# Prototipo_3X.net
KiCad netlist of a schematic drawn in EAGLE
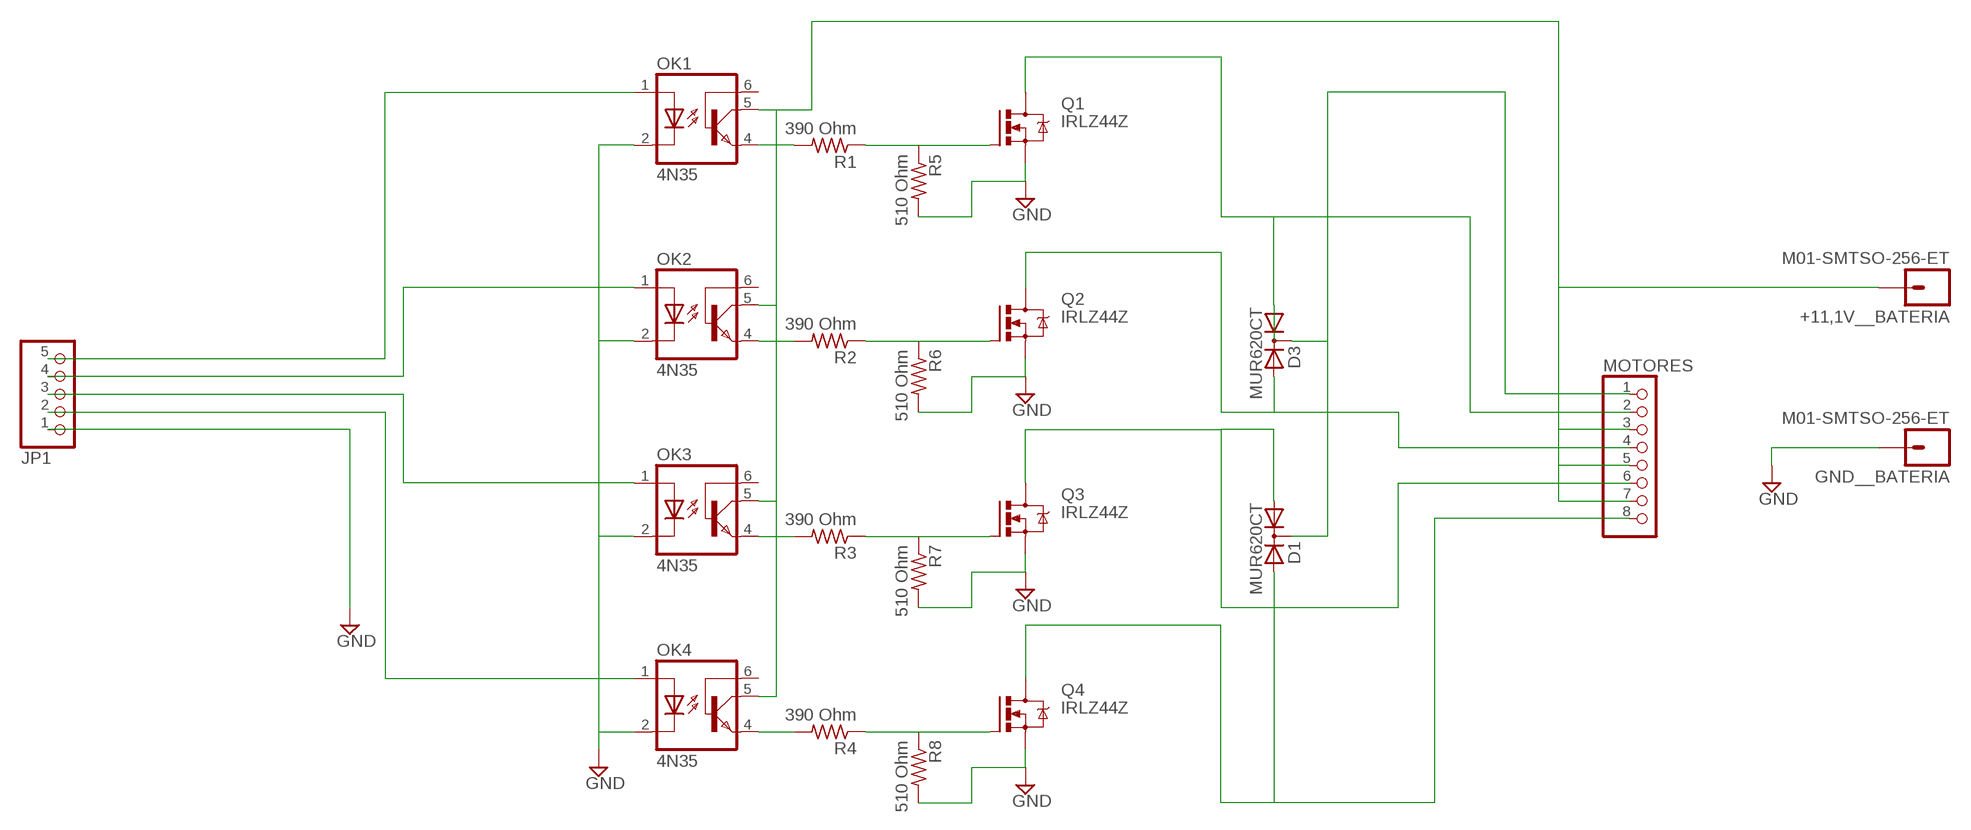
[diagram p0: schematic, sheet 1]

(export (version "E")
  (design (tool "Eeschema 10.0.6"))
  (components
    (comp (ref "+11,1V__BATERIA")
      (value "M01-SMTSO-256-ET")
      (footprint "eagle-import:SMTSO-256-ET")
      (libsource (lib "eagle-import") (part "M01-SMTSO-256-ET"))
    )
    (comp (ref "D1")
      (value "MUR620CT")
      (footprint "eagle-import:TO220AB")
      (libsource (lib "eagle-import") (part "MUR620CT"))
    )
    (comp (ref "D3")
      (value "MUR620CT")
      (footprint "eagle-import:TO220AB")
      (libsource (lib "eagle-import") (part "MUR620CT"))
    )
    (comp (ref "GND__BATERIA")
      (value "M01-SMTSO-256-ET")
      (footprint "eagle-import:SMTSO-256-ET")
      (libsource (lib "eagle-import") (part "M01-SMTSO-256-ET"))
    )
    (comp (ref "JP1")
      (value "PINHD-1X5/90")
      (footprint "eagle-import:1X05_90")
      (libsource (lib "eagle-import") (part "PINHD-1X5/90"))
    )
    (comp (ref "MOTORES")
      (value "PINHD-1X8/90")
      (footprint "eagle-import:1X08_90")
      (libsource (lib "eagle-import") (part "PINHD-1X8/90"))
    )
    (comp (ref "OK1")
      (value "4N35")
      (footprint "eagle-import:DIL06")
      (fields (field (name "MF") "FAIRCHILD SEMICONDUCTOR"))
      (libsource (lib "eagle-import") (part "4N35"))
    )
    (comp (ref "OK2")
      (value "4N35")
      (footprint "eagle-import:DIL06")
      (fields (field (name "MF") "FAIRCHILD SEMICONDUCTOR"))
      (libsource (lib "eagle-import") (part "4N35"))
    )
    (comp (ref "OK3")
      (value "4N35")
      (footprint "eagle-import:DIL06")
      (fields (field (name "MF") "FAIRCHILD SEMICONDUCTOR"))
      (libsource (lib "eagle-import") (part "4N35"))
    )
    (comp (ref "OK4")
      (value "4N35")
      (footprint "eagle-import:DIL06")
      (fields (field (name "MF") "FAIRCHILD SEMICONDUCTOR"))
      (libsource (lib "eagle-import") (part "4N35"))
    )
    (comp (ref "Q1")
      (value "IRLZ44Z")
      (footprint "eagle-import:TO220BH")
      (libsource (lib "eagle-import") (part "IRLZ44Z"))
    )
    (comp (ref "Q2")
      (value "IRLZ44Z")
      (footprint "eagle-import:TO220BH")
      (libsource (lib "eagle-import") (part "IRLZ44Z"))
    )
    (comp (ref "Q3")
      (value "IRLZ44Z")
      (footprint "eagle-import:TO220BH")
      (libsource (lib "eagle-import") (part "IRLZ44Z"))
    )
    (comp (ref "Q4")
      (value "IRLZ44Z")
      (footprint "eagle-import:TO220BH")
      (libsource (lib "eagle-import") (part "IRLZ44Z"))
    )
    (comp (ref "R1")
      (value "390 Ohm")
      (footprint "eagle-import:0207_7")
      (libsource (lib "eagle-import") (part "R-US_0207/7"))
    )
    (comp (ref "R2")
      (value "390 Ohm")
      (footprint "eagle-import:0207_7")
      (libsource (lib "eagle-import") (part "R-US_0207/7"))
    )
    (comp (ref "R3")
      (value "390 Ohm")
      (footprint "eagle-import:0207_7")
      (libsource (lib "eagle-import") (part "R-US_0207/7"))
    )
    (comp (ref "R4")
      (value "390 Ohm")
      (footprint "eagle-import:0207_7")
      (libsource (lib "eagle-import") (part "R-US_0207/7"))
    )
    (comp (ref "R5")
      (value "510 Ohm")
      (footprint "eagle-import:0207_7")
      (libsource (lib "eagle-import") (part "R-US_0207/7"))
    )
    (comp (ref "R6")
      (value "510 Ohm")
      (footprint "eagle-import:0207_7")
      (libsource (lib "eagle-import") (part "R-US_0207/7"))
    )
    (comp (ref "R7")
      (value "510 Ohm")
      (footprint "eagle-import:0207_7")
      (libsource (lib "eagle-import") (part "R-US_0207/7"))
    )
    (comp (ref "R8")
      (value "510 Ohm")
      (footprint "eagle-import:0207_7")
      (libsource (lib "eagle-import") (part "R-US_0207/7"))
    )
  )
  (nets
    (net (code "1") (name "GND") (class "Default")
      (node (ref "GND__BATERIA") (pin "P$1") (pinfunction "1_P$1") (pintype "passive"))
      (node (ref "JP1") (pin "1") (pinfunction "1_1") (pintype "passive"))
      (node (ref "OK1") (pin "2") (pinfunction "C_2") (pintype "passive"))
      (node (ref "OK2") (pin "2") (pinfunction "C_2") (pintype "passive"))
      (node (ref "OK3") (pin "2") (pinfunction "C_2") (pintype "passive"))
      (node (ref "OK4") (pin "2") (pinfunction "C_2") (pintype "passive"))
      (node (ref "Q1") (pin "S") (pinfunction "S_S") (pintype "passive"))
      (node (ref "Q2") (pin "S") (pinfunction "S_S") (pintype "passive"))
      (node (ref "Q3") (pin "S") (pinfunction "S_S") (pintype "passive"))
      (node (ref "Q4") (pin "S") (pinfunction "S_S") (pintype "passive"))
      (node (ref "R5") (pin "2") (pinfunction "2_2") (pintype "passive"))
      (node (ref "R6") (pin "2") (pinfunction "2_2") (pintype "passive"))
      (node (ref "R7") (pin "2") (pinfunction "2_2") (pintype "passive"))
      (node (ref "R8") (pin "2") (pinfunction "2_2") (pintype "passive"))
    )
    (net (code "2") (name "Net-(+11,1V__BATERIA-1)") (class "Default")
      (node (ref "+11,1V__BATERIA") (pin "P$1") (pinfunction "1_P$1") (pintype "passive"))
      (node (ref "D1") (pin "C") (pinfunction "C_C") (pintype "passive"))
      (node (ref "D3") (pin "C") (pinfunction "C_C") (pintype "passive"))
      (node (ref "MOTORES") (pin "1") (pinfunction "1_1") (pintype "passive"))
      (node (ref "MOTORES") (pin "3") (pinfunction "3_3") (pintype "passive"))
      (node (ref "MOTORES") (pin "5") (pinfunction "5_5") (pintype "passive"))
      (node (ref "MOTORES") (pin "7") (pinfunction "7_7") (pintype "passive"))
      (node (ref "OK1") (pin "5") (pinfunction "COL_5") (pintype "passive"))
      (node (ref "OK2") (pin "5") (pinfunction "COL_5") (pintype "passive"))
      (node (ref "OK3") (pin "5") (pinfunction "COL_5") (pintype "passive"))
      (node (ref "OK4") (pin "5") (pinfunction "COL_5") (pintype "passive"))
    )
    (net (code "3") (name "Net-(D1-PadA1)") (class "Default")
      (node (ref "D1") (pin "A1") (pinfunction "A1_A1") (pintype "passive"))
      (node (ref "MOTORES") (pin "6") (pinfunction "6_6") (pintype "passive"))
      (node (ref "Q3") (pin "D") (pinfunction "D_D") (pintype "passive"))
    )
    (net (code "4") (name "Net-(D1-PadA2)") (class "Default")
      (node (ref "D1") (pin "A2") (pinfunction "A2_A2") (pintype "passive"))
      (node (ref "MOTORES") (pin "8") (pinfunction "8_8") (pintype "passive"))
      (node (ref "Q4") (pin "D") (pinfunction "D_D") (pintype "passive"))
    )
    (net (code "5") (name "Net-(D3-PadA1)") (class "Default")
      (node (ref "D3") (pin "A1") (pinfunction "A1_A1") (pintype "passive"))
      (node (ref "MOTORES") (pin "2") (pinfunction "2_2") (pintype "passive"))
      (node (ref "Q1") (pin "D") (pinfunction "D_D") (pintype "passive"))
    )
    (net (code "6") (name "Net-(D3-PadA2)") (class "Default")
      (node (ref "D3") (pin "A2") (pinfunction "A2_A2") (pintype "passive"))
      (node (ref "MOTORES") (pin "4") (pinfunction "4_4") (pintype "passive"))
      (node (ref "Q2") (pin "D") (pinfunction "D_D") (pintype "passive"))
    )
    (net (code "7") (name "Net-(OK1-A)") (class "Default")
      (node (ref "JP1") (pin "5") (pinfunction "5_5") (pintype "passive"))
      (node (ref "OK1") (pin "1") (pinfunction "A_1") (pintype "passive"))
    )
    (net (code "8") (name "Net-(OK1-EMI)") (class "Default")
      (node (ref "OK1") (pin "4") (pinfunction "EMI_4") (pintype "passive"))
      (node (ref "R1") (pin "2") (pinfunction "2_2") (pintype "passive"))
    )
    (net (code "9") (name "Net-(OK2-A)") (class "Default")
      (node (ref "JP1") (pin "4") (pinfunction "4_4") (pintype "passive"))
      (node (ref "OK2") (pin "1") (pinfunction "A_1") (pintype "passive"))
    )
    (net (code "10") (name "Net-(OK2-EMI)") (class "Default")
      (node (ref "OK2") (pin "4") (pinfunction "EMI_4") (pintype "passive"))
      (node (ref "R2") (pin "2") (pinfunction "2_2") (pintype "passive"))
    )
    (net (code "11") (name "Net-(OK3-A)") (class "Default")
      (node (ref "JP1") (pin "3") (pinfunction "3_3") (pintype "passive"))
      (node (ref "OK3") (pin "1") (pinfunction "A_1") (pintype "passive"))
    )
    (net (code "12") (name "Net-(OK3-EMI)") (class "Default")
      (node (ref "OK3") (pin "4") (pinfunction "EMI_4") (pintype "passive"))
      (node (ref "R3") (pin "2") (pinfunction "2_2") (pintype "passive"))
    )
    (net (code "13") (name "Net-(OK4-A)") (class "Default")
      (node (ref "JP1") (pin "2") (pinfunction "2_2") (pintype "passive"))
      (node (ref "OK4") (pin "1") (pinfunction "A_1") (pintype "passive"))
    )
    (net (code "14") (name "Net-(OK4-EMI)") (class "Default")
      (node (ref "OK4") (pin "4") (pinfunction "EMI_4") (pintype "passive"))
      (node (ref "R4") (pin "2") (pinfunction "2_2") (pintype "passive"))
    )
    (net (code "15") (name "Net-(Q1-PadG)") (class "Default")
      (node (ref "Q1") (pin "G") (pinfunction "G_G") (pintype "passive"))
      (node (ref "R1") (pin "1") (pinfunction "1_1") (pintype "passive"))
      (node (ref "R5") (pin "1") (pinfunction "1_1") (pintype "passive"))
    )
    (net (code "16") (name "Net-(Q2-PadG)") (class "Default")
      (node (ref "Q2") (pin "G") (pinfunction "G_G") (pintype "passive"))
      (node (ref "R2") (pin "1") (pinfunction "1_1") (pintype "passive"))
      (node (ref "R6") (pin "1") (pinfunction "1_1") (pintype "passive"))
    )
    (net (code "17") (name "Net-(Q3-PadG)") (class "Default")
      (node (ref "Q3") (pin "G") (pinfunction "G_G") (pintype "passive"))
      (node (ref "R3") (pin "1") (pinfunction "1_1") (pintype "passive"))
      (node (ref "R7") (pin "1") (pinfunction "1_1") (pintype "passive"))
    )
    (net (code "18") (name "Net-(Q4-PadG)") (class "Default")
      (node (ref "Q4") (pin "G") (pinfunction "G_G") (pintype "passive"))
      (node (ref "R4") (pin "1") (pinfunction "1_1") (pintype "passive"))
      (node (ref "R8") (pin "1") (pinfunction "1_1") (pintype "passive"))
    )
    (net (code "19") (name "unconnected-(OK1-BAS-Pad6)") (class "Default")
      (node (ref "OK1") (pin "6") (pinfunction "BAS_6") (pintype "passive"))
    )
    (net (code "20") (name "unconnected-(OK2-BAS-Pad6)") (class "Default")
      (node (ref "OK2") (pin "6") (pinfunction "BAS_6") (pintype "passive"))
    )
    (net (code "21") (name "unconnected-(OK3-BAS-Pad6)") (class "Default")
      (node (ref "OK3") (pin "6") (pinfunction "BAS_6") (pintype "passive"))
    )
    (net (code "22") (name "unconnected-(OK4-BAS-Pad6)") (class "Default")
      (node (ref "OK4") (pin "6") (pinfunction "BAS_6") (pintype "passive"))
    )
  )
)
